# tm4cShield_v2_0.net
KiCad netlist of a schematic drawn in EAGLE
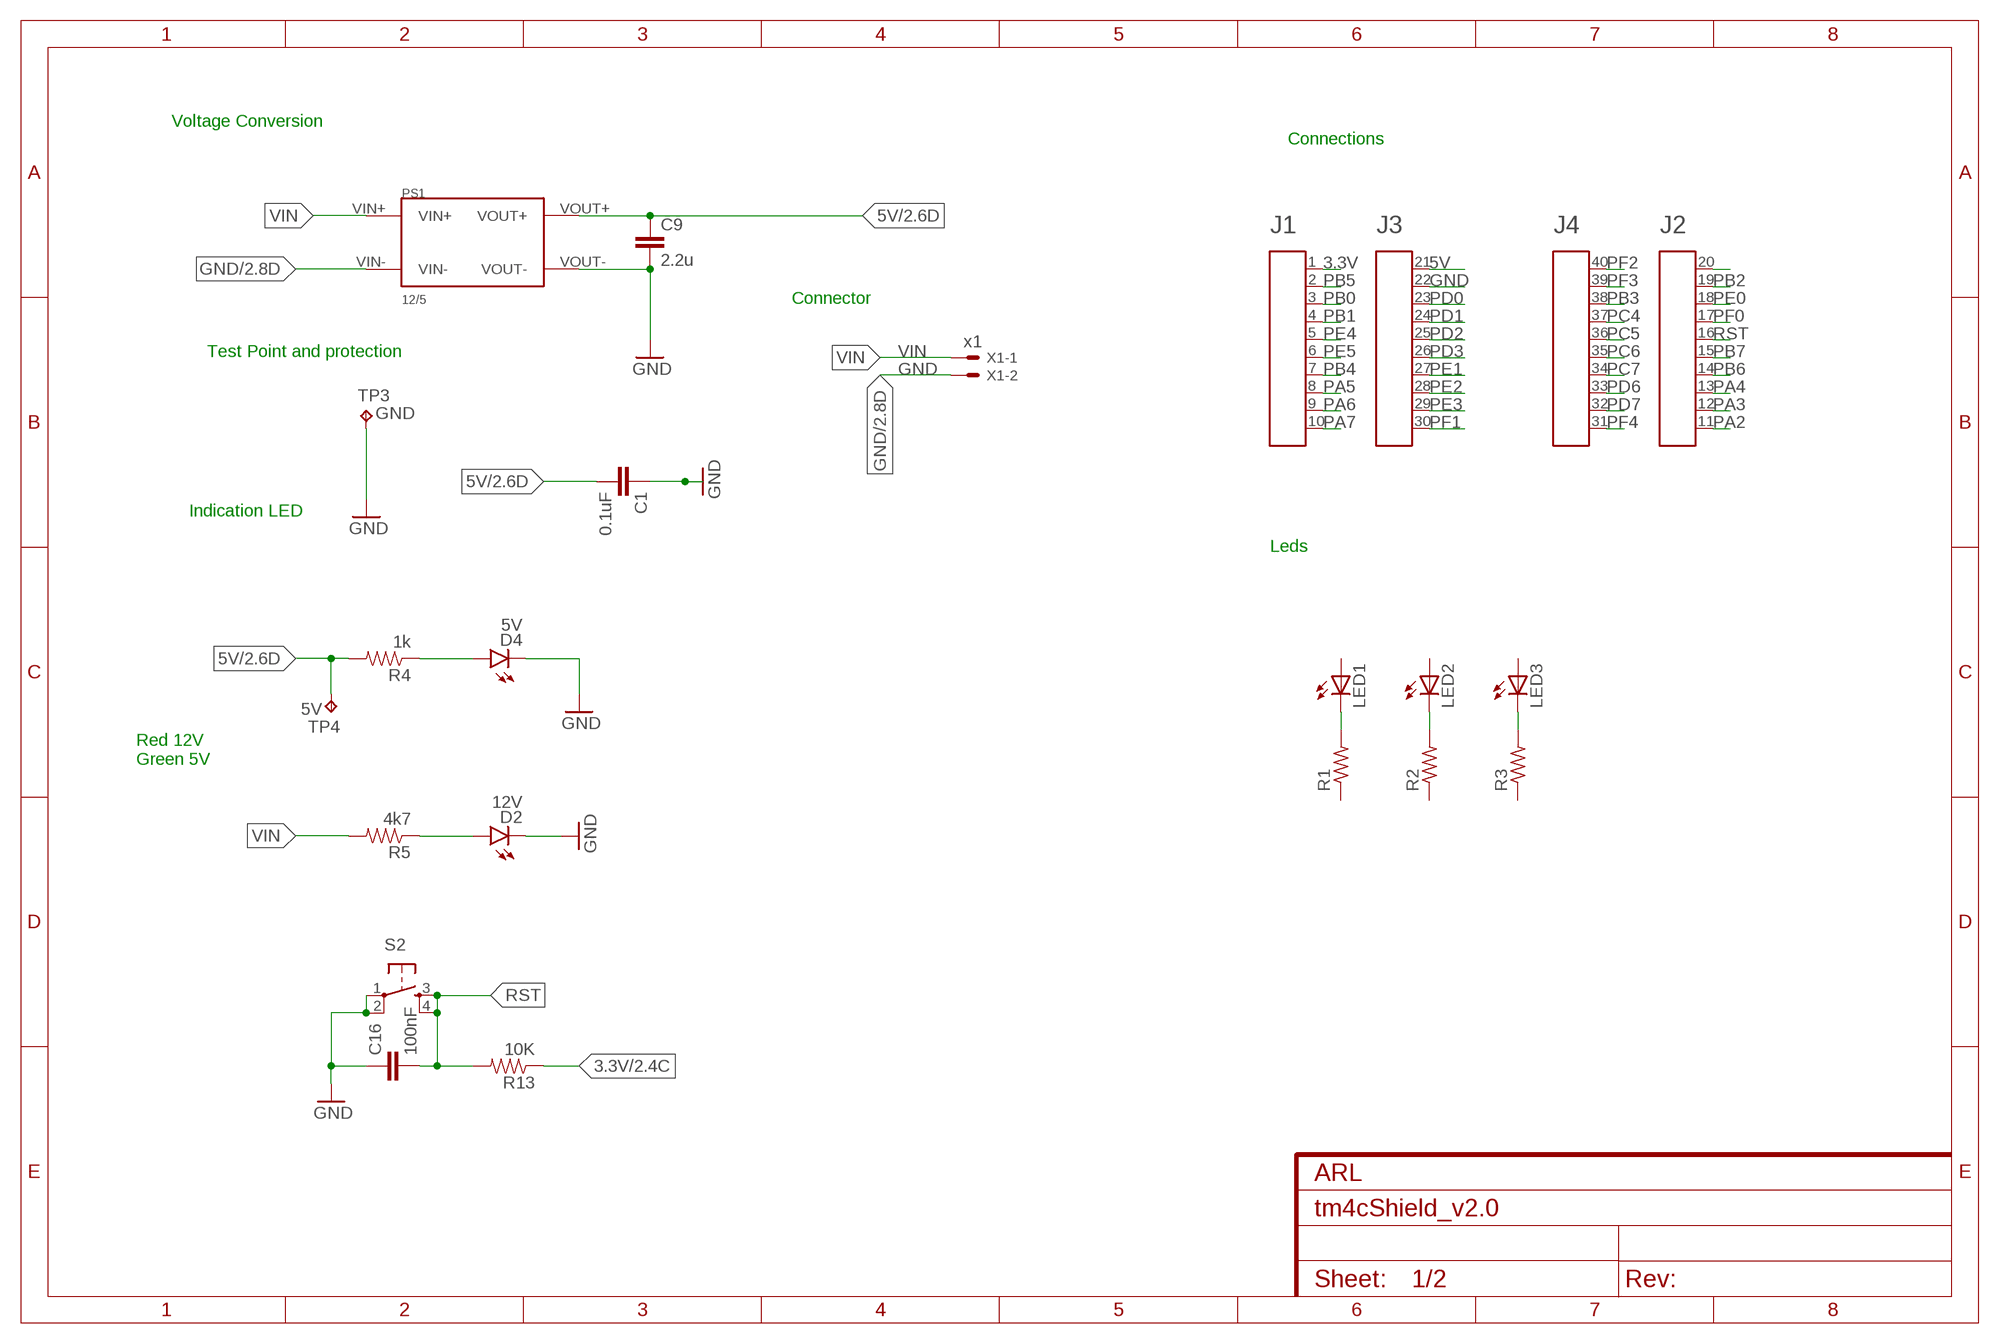
[diagram p0: schematic, sheet 1]
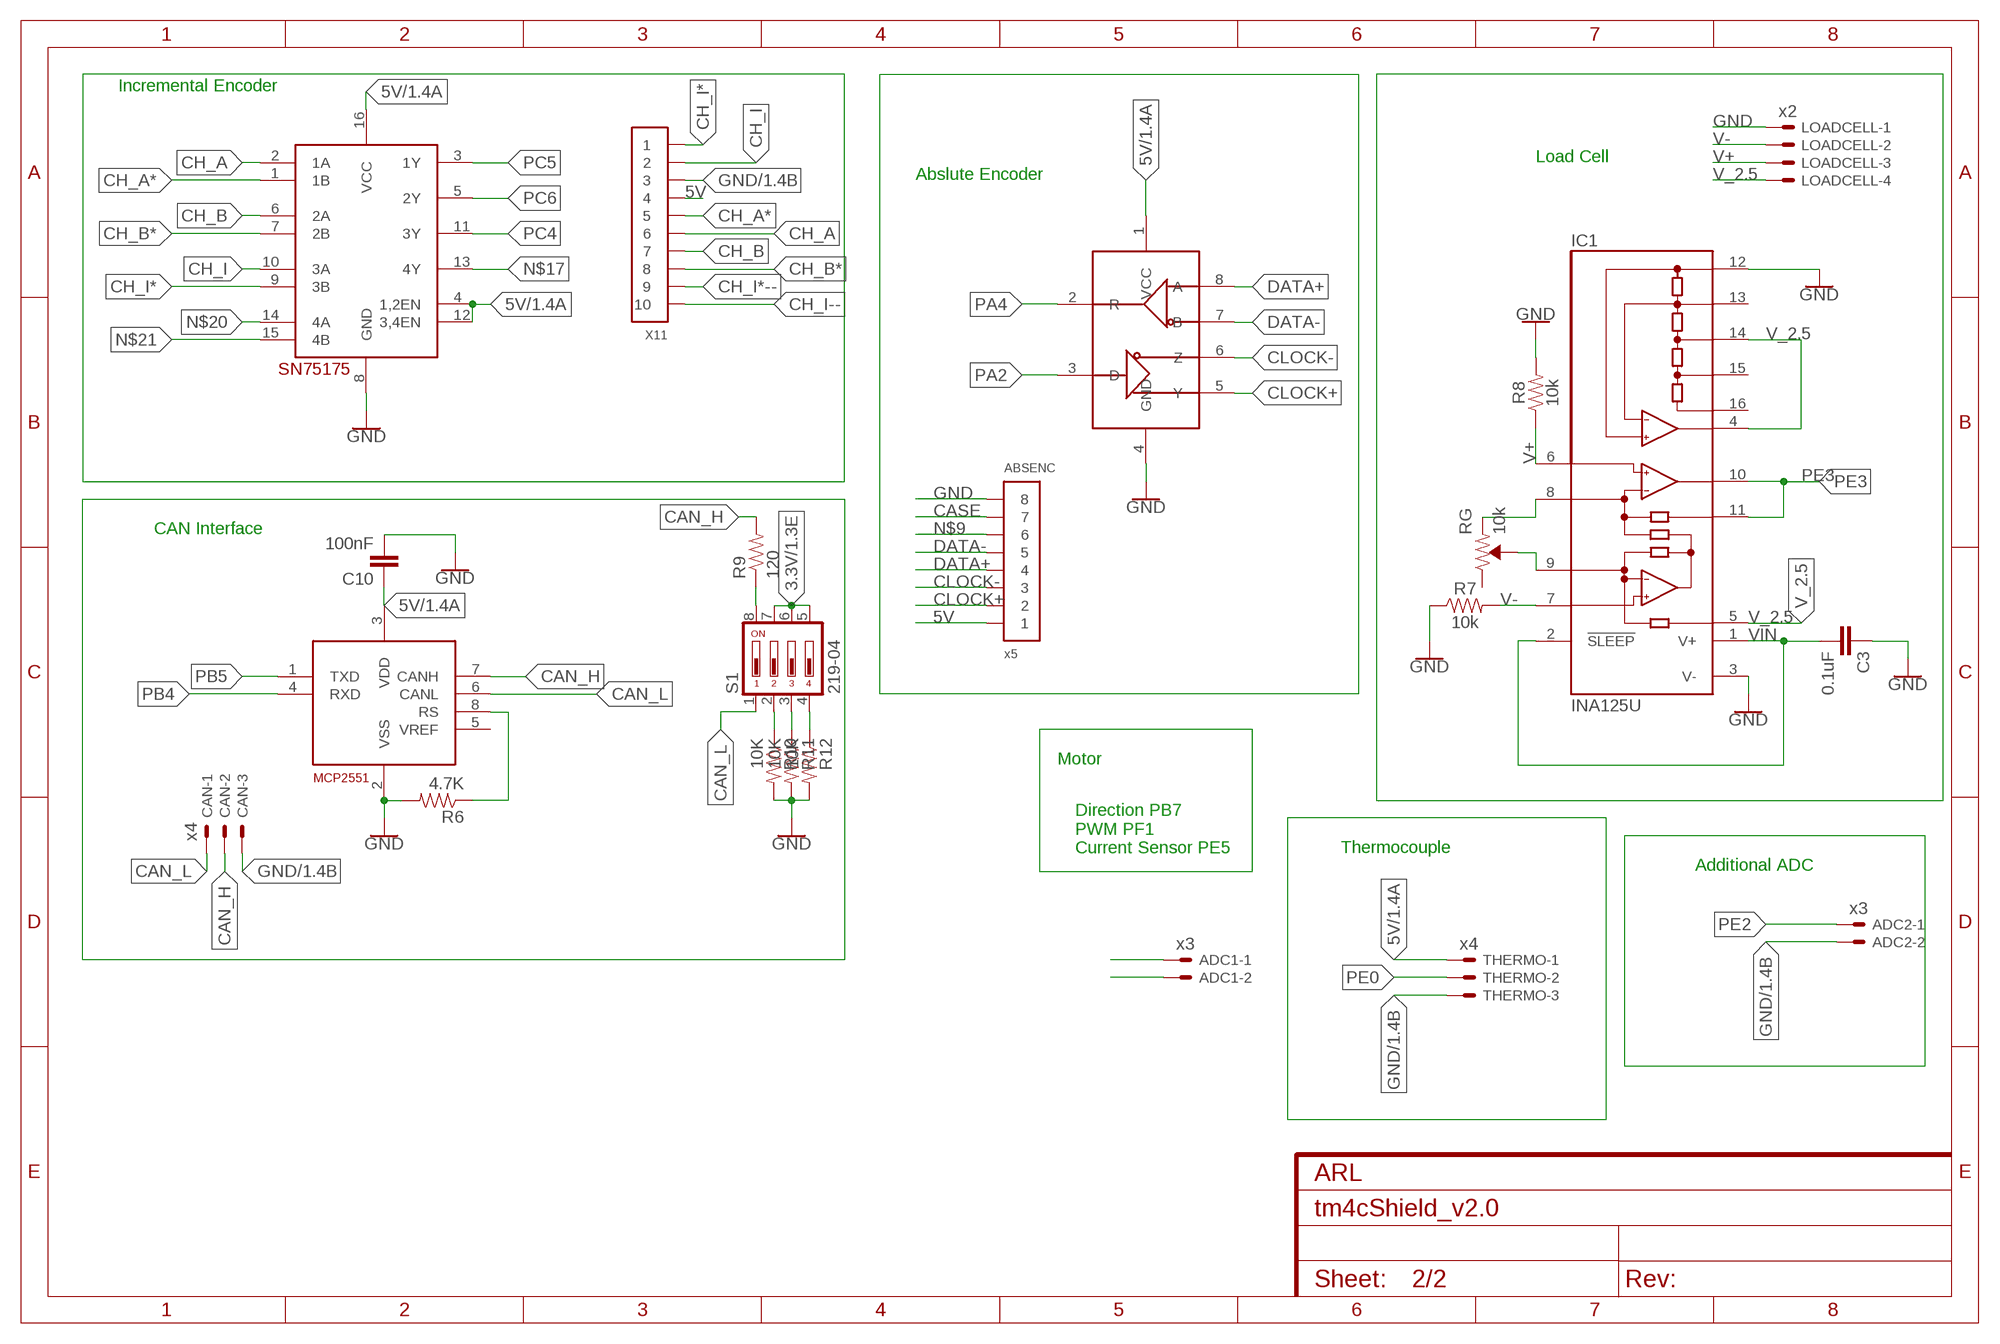
[diagram p1: schematic, sheet 2]

(export (version "E")
  (design (tool "Eeschema 10.0.6"))
  (components
    (comp (ref "ABSENC")
      (value "x5")
      (footprint "eagle-import:PB-53261-08")
      (fields (field (name "PARTNO") "0532610871"))
      (libsource (lib "eagle-import") (part "CONN_8-1-53261"))
    )
    (comp (ref "ADC1")
      (value "x3")
      (footprint "eagle-import:53261-02")
      (libsource (lib "eagle-import") (part "53?-02261"))
    )
    (comp (ref "ADC2")
      (value "x3")
      (footprint "eagle-import:53261-02")
      (libsource (lib "eagle-import") (part "53?-02261"))
    )
    (comp (ref "C3")
      (value "0.1uF")
      (footprint "eagle-import:0603")
      (libsource (lib "eagle-import") (part "0.1UF-0603-25V-(+80/-20%)"))
    )
    (comp (ref "C10")
      (value "100nF")
      (footprint "eagle-import:0603-CAP")
      (fields (field (name "PARTNO") "C1608X7R1E104K"))
      (libsource (lib "eagle-import") (part "CAP0603-CAP"))
    )
    (comp (ref "CAN")
      (value "x4")
      (footprint "eagle-import:53261-03")
      (fields (field (name "MF") "MOLEX") (field (name "MPN") "53261-0390"))
      (libsource (lib "eagle-import") (part "53?-03261"))
    )
    (comp (ref "IC1")
      (value "INA125U")
      (footprint "eagle-import:SO16-1")
      (fields (field (name "MF") "TEXAS INSTRUMENT CONNECTORS"))
      (libsource (lib "eagle-import") (part "INA125U"))
    )
    (comp (ref "LOADCELL")
      (value "x2")
      (footprint "eagle-import:53261-04")
      (libsource (lib "eagle-import") (part "53?-04261"))
    )
    (comp (ref "R6")
      (value "4.7K")
      (footprint "eagle-import:0603-RES")
      (fields (field (name "PARTNO") "ERJ-3EKF4701V"))
      (libsource (lib "eagle-import") (part "RESISTOR0603-RES"))
    )
    (comp (ref "R7")
      (value "10k")
      (footprint "eagle-import:0603")
      (libsource (lib "eagle-import") (part "0.05OHM-0603-1/5W-1%"))
    )
    (comp (ref "R8")
      (value "10k")
      (footprint "eagle-import:0603")
      (libsource (lib "eagle-import") (part "0.05OHM-0603-1/5W-1%"))
    )
    (comp (ref "R9")
      (value "120")
      (footprint "eagle-import:0603-RES")
      (fields (field (name "PARTNO") "ERJ-3GEYJ121V"))
      (libsource (lib "eagle-import") (part "RESISTOR0603-RES"))
    )
    (comp (ref "R10")
      (value "10K")
      (footprint "eagle-import:0603-RES")
      (fields (field (name "PARTNO") "ERJ-3EKF1002V"))
      (libsource (lib "eagle-import") (part "RESISTOR0603-RES"))
    )
    (comp (ref "R11")
      (value "10K")
      (footprint "eagle-import:0603-RES")
      (fields (field (name "PARTNO") "ERJ-3EKF1002V"))
      (libsource (lib "eagle-import") (part "RESISTOR0603-RES"))
    )
    (comp (ref "R12")
      (value "10K")
      (footprint "eagle-import:0603-RES")
      (fields (field (name "PARTNO") "ERJ-3EKF1002V"))
      (libsource (lib "eagle-import") (part "RESISTOR0603-RES"))
    )
    (comp (ref "RG")
      (value "10k")
      (footprint "eagle-import:TRIMPOT-PTH-3386U")
      (libsource (lib "eagle-import") (part "TRIMPOT-PTH-10MM-KNOB-1/2W-10%"))
    )
    (comp (ref "S1")
      (value "219-04")
      (footprint "eagle-import:CTS-219-04")
      (fields (field (name "PARTNO") "219-4LPST"))
      (libsource (lib "eagle-import") (part "219-04"))
    )
    (comp (ref "THERMO")
      (value "x4")
      (footprint "eagle-import:53261-03")
      (fields (field (name "MF") "MOLEX") (field (name "MPN") "53261-0390"))
      (libsource (lib "eagle-import") (part "53?-03261"))
    )
    (comp (ref "U$2")
      (value "SN75175")
      (footprint "eagle-import:SOIC16")
      (fields (field (name "PARTNO") "SN75175DR"))
      (libsource (lib "eagle-import") (part "SN75175"))
    )
    (comp (ref "U$4")
      (value "SP490")
      (footprint "eagle-import:SOIC8")
      (fields (field (name "PARTNO") "SP490CN-L"))
      (libsource (lib "eagle-import") (part "SP490"))
    )
    (comp (ref "U2")
      (value "MCP2551")
      (footprint "eagle-import:SOIC8")
      (fields (field (name "PARTNO") "MCP2551-I/SN"))
      (libsource (lib "eagle-import") (part "MCP2551"))
    )
    (comp (ref "X11")
      (value "CONN_10-1-53261")
      (footprint "eagle-import:PB-53261-10")
      (fields (field (name "PARTNO") "0532611071"))
      (libsource (lib "eagle-import") (part "CONN_10-1-53261"))
    )
    (comp (ref "A1")
      (value "HEADER4X10-BOOSTERPACK")
      (footprint "eagle-import:4X10-BOOSTERPACK")
      (libsource (lib "eagle-import") (part "HEADER4X10-BOOSTERPACK"))
    )
    (comp (ref "C1")
      (value "0.1uF")
      (footprint "eagle-import:0603")
      (libsource (lib "eagle-import") (part "0.1UF-0603-25V-(+80/-20%)"))
    )
    (comp (ref "C9")
      (value "2.2u")
      (footprint "eagle-import:0603-CAP")
      (fields (field (name "MPN") "GRM188R61H225KE11D"))
      (libsource (lib "eagle-import") (part "2.2U_CAPACITOR_0603"))
    )
    (comp (ref "C16")
      (value "100nF")
      (footprint "eagle-import:0603-CAP")
      (fields (field (name "PARTNO") "C1608X7R1E104K"))
      (libsource (lib "eagle-import") (part "SparkFun-Passives_CAP0603-CAP"))
    )
    (comp (ref "D2")
      (value "12V")
      (footprint "eagle-import:LED-0603")
      (fields (field (name "MPN") "LY L296-Q2R2-26-Z"))
      (libsource (lib "eagle-import") (part "YELLOW_LED_0603"))
    )
    (comp (ref "D4")
      (value "5V")
      (footprint "eagle-import:LED-0603")
      (fields (field (name "MPN") "LB L293-M2P1-36-1-Z"))
      (libsource (lib "eagle-import") (part "BLUE_LED_0603"))
    )
    (comp (ref "LED1")
      (value "LED0603")
      (footprint "eagle-import:LED-0603")
      (libsource (lib "eagle-import") (part "LED0603"))
    )
    (comp (ref "LED2")
      (value "LED0603")
      (footprint "eagle-import:LED-0603")
      (libsource (lib "eagle-import") (part "LED0603"))
    )
    (comp (ref "LED3")
      (value "LED0603")
      (footprint "eagle-import:LED-0603")
      (libsource (lib "eagle-import") (part "LED0603"))
    )
    (comp (ref "PS1")
      (value "12/5")
      (footprint "eagle-import:MURATA_NMG")
      (fields (field (name "MPN") "NMG2405SC "))
      (libsource (lib "eagle-import") (part "MURATA_NMG2405SC"))
    )
    (comp (ref "R1")
      (value "RESISTOR_0603")
      (footprint "eagle-import:RESC0603")
      (libsource (lib "eagle-import") (part "RESISTOR_0603"))
    )
    (comp (ref "R2")
      (value "RESISTOR_0603")
      (footprint "eagle-import:RESC0603")
      (libsource (lib "eagle-import") (part "RESISTOR_0603"))
    )
    (comp (ref "R3")
      (value "RESISTOR_0603")
      (footprint "eagle-import:RESC0603")
      (libsource (lib "eagle-import") (part "RESISTOR_0603"))
    )
    (comp (ref "R4")
      (value "1k")
      (footprint "eagle-import:0603-RES")
      (fields (field (name "MPN") "CRCW06031K00FKEA"))
      (libsource (lib "eagle-import") (part "1K_RESISTOR_0603"))
    )
    (comp (ref "R5")
      (value "4k7")
      (footprint "eagle-import:0603-RES")
      (fields (field (name "MPN") "CRCW06034K70FKEA"))
      (libsource (lib "eagle-import") (part "4K7_RESISTOR_0603"))
    )
    (comp (ref "R13")
      (value "10K")
      (footprint "eagle-import:0603-RES")
      (fields (field (name "PARTNO") "ERJ-3EKF1002V"))
      (libsource (lib "eagle-import") (part "SparkFun-Passives_RESISTOR0603-RES"))
    )
    (comp (ref "S2")
      (value "TAC_SWITCHPTH")
      (footprint "eagle-import:TACTILE-PTH")
      (fields (field (name "PARTNO") "B3F-1005"))
      (libsource (lib "eagle-import") (part "TAC_SWITCHPTH"))
    )
    (comp (ref "TP3")
      (value "GND")
      (footprint "eagle-import:5000_SERIES_TESTPOINT")
      (fields (field (name "MPN") "5002"))
      (libsource (lib "eagle-import") (part "TP5000"))
    )
    (comp (ref "TP4")
      (value "5V")
      (footprint "eagle-import:5000_SERIES_TESTPOINT")
      (fields (field (name "MPN") "5002"))
      (libsource (lib "eagle-import") (part "TP5000"))
    )
    (comp (ref "X1")
      (value "x1")
      (footprint "eagle-import:53261-02")
      (libsource (lib "eagle-import") (part "53?-02261"))
    )
  )
  (nets
    (net (code "1") (name "3.3V") (class "Default")
      (node (ref "A1") (pin "1") (pinfunction "P$1_1") (pintype "bidirectional"))
      (node (ref "R13") (pin "1") (pinfunction "1_1") (pintype "passive"))
      (node (ref "S1") (pin "5") (pinfunction "5_5") (pintype "passive"))
      (node (ref "S1") (pin "6") (pinfunction "6_6") (pintype "passive"))
      (node (ref "S1") (pin "7") (pinfunction "7_7") (pintype "passive"))
    )
    (net (code "2") (name "5V") (class "Default")
      (node (ref "A1") (pin "21") (pinfunction "P$21_21") (pintype "bidirectional"))
      (node (ref "ABSENC") (pin "1") (pinfunction "1_1") (pintype "bidirectional"))
      (node (ref "C1") (pin "2") (pinfunction "2_2") (pintype "passive"))
      (node (ref "C10") (pin "1") (pinfunction "1_1") (pintype "passive"))
      (node (ref "C9") (pin "1") (pinfunction "1_1") (pintype "passive"))
      (node (ref "PS1") (pin "VOUT+") (pinfunction "VOUT+_VOUT+") (pintype "bidirectional"))
      (node (ref "R4") (pin "2") (pinfunction "2_2") (pintype "passive"))
      (node (ref "THERMO") (pin "1") (pinfunction "S_1") (pintype "passive"))
      (node (ref "TP4") (pin "P$1") (pinfunction "TP_P$1") (pintype "input"))
      (node (ref "U$2") (pin "12") (pinfunction "3,4EN_12") (pintype "bidirectional"))
      (node (ref "U$2") (pin "16") (pinfunction "VCC_16") (pintype "bidirectional"))
      (node (ref "U$2") (pin "4") (pinfunction "1,2EN_4") (pintype "bidirectional"))
      (node (ref "U$4") (pin "1") (pinfunction "VCC_1") (pintype "bidirectional"))
      (node (ref "U2") (pin "3") (pinfunction "VDD_3") (pintype "bidirectional"))
      (node (ref "X11") (pin "4") (pinfunction "4_4") (pintype "bidirectional"))
    )
    (net (code "3") (name "CAN_H") (class "Default")
      (node (ref "CAN") (pin "2") (pinfunction "S_2") (pintype "passive"))
      (node (ref "R9") (pin "2") (pinfunction "2_2") (pintype "passive"))
      (node (ref "U2") (pin "7") (pinfunction "CANH_7") (pintype "bidirectional"))
    )
    (net (code "4") (name "CAN_L") (class "Default")
      (node (ref "CAN") (pin "1") (pinfunction "S_1") (pintype "passive"))
      (node (ref "S1") (pin "1") (pinfunction "1_1") (pintype "passive"))
      (node (ref "U2") (pin "6") (pinfunction "CANL_6") (pintype "bidirectional"))
    )
    (net (code "5") (name "CASE") (class "Default")
      (node (ref "ABSENC") (pin "7") (pinfunction "7_7") (pintype "bidirectional"))
    )
    (net (code "6") (name "CH_A") (class "Default")
      (node (ref "U$2") (pin "2") (pinfunction "1A_2") (pintype "bidirectional"))
      (node (ref "X11") (pin "6") (pinfunction "6_6") (pintype "bidirectional"))
    )
    (net (code "7") (name "CH_A*") (class "Default")
      (node (ref "U$2") (pin "1") (pinfunction "1B_1") (pintype "bidirectional"))
      (node (ref "X11") (pin "5") (pinfunction "5_5") (pintype "bidirectional"))
    )
    (net (code "8") (name "CH_B") (class "Default")
      (node (ref "U$2") (pin "6") (pinfunction "2A_6") (pintype "bidirectional"))
      (node (ref "X11") (pin "7") (pinfunction "7_7") (pintype "bidirectional"))
    )
    (net (code "9") (name "CH_B*") (class "Default")
      (node (ref "U$2") (pin "7") (pinfunction "2B_7") (pintype "bidirectional"))
      (node (ref "X11") (pin "8") (pinfunction "8_8") (pintype "bidirectional"))
    )
    (net (code "10") (name "CH_I") (class "Default")
      (node (ref "U$2") (pin "10") (pinfunction "3A_10") (pintype "bidirectional"))
      (node (ref "X11") (pin "2") (pinfunction "2_2") (pintype "bidirectional"))
    )
    (net (code "11") (name "CH_I*") (class "Default")
      (node (ref "U$2") (pin "9") (pinfunction "3B_9") (pintype "bidirectional"))
      (node (ref "X11") (pin "1") (pinfunction "1_1") (pintype "bidirectional"))
    )
    (net (code "12") (name "CH_I*--") (class "Default")
      (node (ref "X11") (pin "9") (pinfunction "9_9") (pintype "bidirectional"))
    )
    (net (code "13") (name "CH_I--") (class "Default")
      (node (ref "X11") (pin "10") (pinfunction "10_10") (pintype "bidirectional"))
    )
    (net (code "14") (name "CLOCK+") (class "Default")
      (node (ref "ABSENC") (pin "2") (pinfunction "2_2") (pintype "bidirectional"))
      (node (ref "U$4") (pin "5") (pinfunction "Y_5") (pintype "bidirectional"))
    )
    (net (code "15") (name "CLOCK-") (class "Default")
      (node (ref "ABSENC") (pin "3") (pinfunction "3_3") (pintype "bidirectional"))
      (node (ref "U$4") (pin "6") (pinfunction "Z_6") (pintype "bidirectional"))
    )
    (net (code "16") (name "DATA+") (class "Default")
      (node (ref "ABSENC") (pin "4") (pinfunction "4_4") (pintype "bidirectional"))
      (node (ref "U$4") (pin "8") (pinfunction "A_8") (pintype "bidirectional"))
    )
    (net (code "17") (name "DATA-") (class "Default")
      (node (ref "ABSENC") (pin "5") (pinfunction "5_5") (pintype "bidirectional"))
      (node (ref "U$4") (pin "7") (pinfunction "B_7") (pintype "bidirectional"))
    )
    (net (code "18") (name "GND") (class "Default")
      (node (ref "A1") (pin "22") (pinfunction "P$22_22") (pintype "bidirectional"))
      (node (ref "ABSENC") (pin "8") (pinfunction "8_8") (pintype "bidirectional"))
      (node (ref "ADC2") (pin "2") (pinfunction "S_2") (pintype "passive"))
      (node (ref "C1") (pin "1") (pinfunction "1_1") (pintype "passive"))
      (node (ref "C10") (pin "2") (pinfunction "2_2") (pintype "passive"))
      (node (ref "C16") (pin "1") (pinfunction "1_1") (pintype "passive"))
      (node (ref "C3") (pin "1") (pinfunction "1_1") (pintype "passive"))
      (node (ref "C9") (pin "2") (pinfunction "2_2") (pintype "passive"))
      (node (ref "CAN") (pin "3") (pinfunction "S_3") (pintype "passive"))
      (node (ref "D2") (pin "C") (pinfunction "C_C") (pintype "passive"))
      (node (ref "D4") (pin "C") (pinfunction "C_C") (pintype "passive"))
      (node (ref "IC1") (pin "12") (pinfunction "REFCOM_12") (pintype "passive"))
      (node (ref "IC1") (pin "3") (pinfunction "V-_3") (pintype "power_in"))
      (node (ref "LOADCELL") (pin "1") (pinfunction "S_1") (pintype "passive"))
      (node (ref "PS1") (pin "VIN-") (pinfunction "VIN-_VIN-") (pintype "bidirectional"))
      (node (ref "PS1") (pin "VOUT-") (pinfunction "VOUT-_VOUT-") (pintype "bidirectional"))
      (node (ref "R10") (pin "2") (pinfunction "2_2") (pintype "passive"))
      (node (ref "R11") (pin "2") (pinfunction "2_2") (pintype "passive"))
      (node (ref "R12") (pin "2") (pinfunction "2_2") (pintype "passive"))
      (node (ref "R6") (pin "2") (pinfunction "2_2") (pintype "passive"))
      (node (ref "R7") (pin "1") (pinfunction "1_1") (pintype "passive"))
      (node (ref "R8") (pin "2") (pinfunction "2_2") (pintype "passive"))
      (node (ref "S2") (pin "1") (pinfunction "1_1") (pintype "passive"))
      (node (ref "S2") (pin "2") (pinfunction "2_2") (pintype "passive"))
      (node (ref "THERMO") (pin "3") (pinfunction "S_3") (pintype "passive"))
      (node (ref "TP3") (pin "P$1") (pinfunction "TP_P$1") (pintype "input"))
      (node (ref "U$2") (pin "8") (pinfunction "GND_8") (pintype "bidirectional"))
      (node (ref "U$4") (pin "4") (pinfunction "GND_4") (pintype "bidirectional"))
      (node (ref "U2") (pin "2") (pinfunction "VSS_2") (pintype "bidirectional"))
      (node (ref "X1") (pin "2") (pinfunction "S_2") (pintype "passive"))
      (node (ref "X11") (pin "3") (pinfunction "3_3") (pintype "bidirectional"))
    )
    (net (code "19") (name "N$9") (class "Default")
      (node (ref "ABSENC") (pin "6") (pinfunction "6_6") (pintype "bidirectional"))
    )
    (net (code "20") (name "N$17") (class "Default")
      (node (ref "U$2") (pin "13") (pinfunction "4Y_13") (pintype "bidirectional"))
    )
    (net (code "21") (name "N$20") (class "Default")
      (node (ref "U$2") (pin "14") (pinfunction "4A_14") (pintype "bidirectional"))
    )
    (net (code "22") (name "N$21") (class "Default")
      (node (ref "U$2") (pin "15") (pinfunction "4B_15") (pintype "bidirectional"))
    )
    (net (code "23") (name "Net-(D2-PadA)") (class "Default")
      (node (ref "D2") (pin "A") (pinfunction "A_A") (pintype "passive"))
      (node (ref "R5") (pin "1") (pinfunction "1_1") (pintype "passive"))
    )
    (net (code "24") (name "Net-(D4-PadA)") (class "Default")
      (node (ref "D4") (pin "A") (pinfunction "A_A") (pintype "passive"))
      (node (ref "R4") (pin "1") (pinfunction "1_1") (pintype "passive"))
    )
    (net (code "25") (name "Net-(LED1-PadC)") (class "Default")
      (node (ref "LED1") (pin "C") (pinfunction "C_C") (pintype "passive"))
      (node (ref "R1") (pin "2") (pinfunction "2_2") (pintype "passive"))
    )
    (net (code "26") (name "Net-(LED2-PadC)") (class "Default")
      (node (ref "LED2") (pin "C") (pinfunction "C_C") (pintype "passive"))
      (node (ref "R2") (pin "2") (pinfunction "2_2") (pintype "passive"))
    )
    (net (code "27") (name "Net-(LED3-PadC)") (class "Default")
      (node (ref "LED3") (pin "C") (pinfunction "C_C") (pintype "passive"))
      (node (ref "R3") (pin "2") (pinfunction "2_2") (pintype "passive"))
    )
    (net (code "28") (name "Net-(R9-Pad1)") (class "Default")
      (node (ref "R9") (pin "1") (pinfunction "1_1") (pintype "passive"))
      (node (ref "S1") (pin "8") (pinfunction "8_8") (pintype "passive"))
    )
    (net (code "29") (name "Net-(R10-Pad1)") (class "Default")
      (node (ref "R10") (pin "1") (pinfunction "1_1") (pintype "passive"))
      (node (ref "S1") (pin "2") (pinfunction "2_2") (pintype "passive"))
    )
    (net (code "30") (name "Net-(R11-Pad1)") (class "Default")
      (node (ref "R11") (pin "1") (pinfunction "1_1") (pintype "passive"))
      (node (ref "S1") (pin "3") (pinfunction "3_3") (pintype "passive"))
    )
    (net (code "31") (name "Net-(R12-Pad1)") (class "Default")
      (node (ref "R12") (pin "1") (pinfunction "1_1") (pintype "passive"))
      (node (ref "S1") (pin "4") (pinfunction "4_4") (pintype "passive"))
    )
    (net (code "32") (name "Net-(RG-CCW)") (class "Default")
      (node (ref "IC1") (pin "8") (pinfunction "RG_8") (pintype "passive"))
      (node (ref "RG") (pin "1") (pinfunction "CCW_1") (pintype "passive"))
    )
    (net (code "33") (name "Net-(RG-WIPER)") (class "Default")
      (node (ref "IC1") (pin "9") (pinfunction "RG_9") (pintype "passive"))
      (node (ref "RG") (pin "2") (pinfunction "WIPER_2") (pintype "passive"))
    )
    (net (code "34") (name "Net-(U2-RS)") (class "Default")
      (node (ref "R6") (pin "1") (pinfunction "1_1") (pintype "passive"))
      (node (ref "U2") (pin "8") (pinfunction "RS_8") (pintype "bidirectional"))
    )
    (net (code "35") (name "PA2") (class "Default")
      (node (ref "A1") (pin "11") (pinfunction "P$11_11") (pintype "bidirectional"))
      (node (ref "U$4") (pin "3") (pinfunction "D_3") (pintype "bidirectional"))
    )
    (net (code "36") (name "PA3") (class "Default")
      (node (ref "A1") (pin "12") (pinfunction "P$12_12") (pintype "bidirectional"))
    )
    (net (code "37") (name "PA4") (class "Default")
      (node (ref "A1") (pin "13") (pinfunction "P$13_13") (pintype "bidirectional"))
      (node (ref "U$4") (pin "2") (pinfunction "R_2") (pintype "bidirectional"))
    )
    (net (code "38") (name "PA5") (class "Default")
      (node (ref "A1") (pin "8") (pinfunction "P$8_8") (pintype "bidirectional"))
    )
    (net (code "39") (name "PA6") (class "Default")
      (node (ref "A1") (pin "9") (pinfunction "P$9_9") (pintype "bidirectional"))
    )
    (net (code "40") (name "PA7") (class "Default")
      (node (ref "A1") (pin "10") (pinfunction "P$10_10") (pintype "bidirectional"))
    )
    (net (code "41") (name "PB0") (class "Default")
      (node (ref "A1") (pin "3") (pinfunction "P$3_3") (pintype "bidirectional"))
    )
    (net (code "42") (name "PB1") (class "Default")
      (node (ref "A1") (pin "4") (pinfunction "P$4_4") (pintype "bidirectional"))
    )
    (net (code "43") (name "PB2") (class "Default")
      (node (ref "A1") (pin "19") (pinfunction "P$19_19") (pintype "bidirectional"))
    )
    (net (code "44") (name "PB3") (class "Default")
      (node (ref "A1") (pin "38") (pinfunction "P$38_38") (pintype "bidirectional"))
    )
    (net (code "45") (name "PB4") (class "Default")
      (node (ref "A1") (pin "7") (pinfunction "P$7_7") (pintype "bidirectional"))
      (node (ref "U2") (pin "4") (pinfunction "RXD_4") (pintype "bidirectional"))
    )
    (net (code "46") (name "PB5") (class "Default")
      (node (ref "A1") (pin "2") (pinfunction "P$2_2") (pintype "bidirectional"))
      (node (ref "U2") (pin "1") (pinfunction "TXD_1") (pintype "bidirectional"))
    )
    (net (code "47") (name "PB6") (class "Default")
      (node (ref "A1") (pin "14") (pinfunction "P$14_14") (pintype "bidirectional"))
    )
    (net (code "48") (name "PB7") (class "Default")
      (node (ref "A1") (pin "15") (pinfunction "P$15_15") (pintype "bidirectional"))
    )
    (net (code "49") (name "PC4") (class "Default")
      (node (ref "A1") (pin "37") (pinfunction "P$37_37") (pintype "bidirectional"))
      (node (ref "U$2") (pin "11") (pinfunction "3Y_11") (pintype "bidirectional"))
    )
    (net (code "50") (name "PC5") (class "Default")
      (node (ref "A1") (pin "36") (pinfunction "P$36_36") (pintype "bidirectional"))
      (node (ref "U$2") (pin "3") (pinfunction "1Y_3") (pintype "bidirectional"))
    )
    (net (code "51") (name "PC6") (class "Default")
      (node (ref "A1") (pin "35") (pinfunction "P$35_35") (pintype "bidirectional"))
      (node (ref "U$2") (pin "5") (pinfunction "2Y_5") (pintype "bidirectional"))
    )
    (net (code "52") (name "PC7") (class "Default")
      (node (ref "A1") (pin "34") (pinfunction "P$34_34") (pintype "bidirectional"))
    )
    (net (code "53") (name "PD0") (class "Default")
      (node (ref "A1") (pin "23") (pinfunction "P$23_23") (pintype "bidirectional"))
    )
    (net (code "54") (name "PD1") (class "Default")
      (node (ref "A1") (pin "24") (pinfunction "P$24_24") (pintype "bidirectional"))
    )
    (net (code "55") (name "PD2") (class "Default")
      (node (ref "A1") (pin "25") (pinfunction "P$25_25") (pintype "bidirectional"))
    )
    (net (code "56") (name "PD3") (class "Default")
      (node (ref "A1") (pin "26") (pinfunction "P$26_26") (pintype "bidirectional"))
    )
    (net (code "57") (name "PD6") (class "Default")
      (node (ref "A1") (pin "33") (pinfunction "P$33_33") (pintype "bidirectional"))
    )
    (net (code "58") (name "PD7") (class "Default")
      (node (ref "A1") (pin "32") (pinfunction "P$32_32") (pintype "bidirectional"))
    )
    (net (code "59") (name "PE0") (class "Default")
      (node (ref "A1") (pin "18") (pinfunction "P$18_18") (pintype "bidirectional"))
      (node (ref "THERMO") (pin "2") (pinfunction "S_2") (pintype "passive"))
    )
    (net (code "60") (name "PE1") (class "Default")
      (node (ref "A1") (pin "27") (pinfunction "P$27_27") (pintype "bidirectional"))
    )
    (net (code "61") (name "PE2") (class "Default")
      (node (ref "A1") (pin "28") (pinfunction "P$28_28") (pintype "bidirectional"))
      (node (ref "ADC2") (pin "1") (pinfunction "S_1") (pintype "passive"))
    )
    (net (code "62") (name "PE3") (class "Default")
      (node (ref "A1") (pin "29") (pinfunction "P$29_29") (pintype "bidirectional"))
      (node (ref "IC1") (pin "10") (pinfunction "OUT_10") (pintype "output"))
      (node (ref "IC1") (pin "11") (pinfunction "SENSE_11") (pintype "passive"))
    )
    (net (code "63") (name "PE4") (class "Default")
      (node (ref "A1") (pin "5") (pinfunction "P$5_5") (pintype "bidirectional"))
    )
    (net (code "64") (name "PE5") (class "Default")
      (node (ref "A1") (pin "6") (pinfunction "P$6_6") (pintype "bidirectional"))
    )
    (net (code "65") (name "PF0") (class "Default")
      (node (ref "A1") (pin "17") (pinfunction "P$17_17") (pintype "bidirectional"))
    )
    (net (code "66") (name "PF1") (class "Default")
      (node (ref "A1") (pin "30") (pinfunction "P$30_30") (pintype "bidirectional"))
    )
    (net (code "67") (name "PF2") (class "Default")
      (node (ref "A1") (pin "40") (pinfunction "P$40_40") (pintype "bidirectional"))
    )
    (net (code "68") (name "PF3") (class "Default")
      (node (ref "A1") (pin "39") (pinfunction "P$39_39") (pintype "bidirectional"))
    )
    (net (code "69") (name "PF4") (class "Default")
      (node (ref "A1") (pin "31") (pinfunction "P$31_31") (pintype "bidirectional"))
    )
    (net (code "70") (name "RST") (class "Default")
      (node (ref "A1") (pin "16") (pinfunction "P$16_16") (pintype "bidirectional"))
      (node (ref "C16") (pin "2") (pinfunction "2_2") (pintype "passive"))
      (node (ref "R13") (pin "2") (pinfunction "2_2") (pintype "passive"))
      (node (ref "S2") (pin "3") (pinfunction "3_3") (pintype "passive"))
      (node (ref "S2") (pin "4") (pinfunction "4_4") (pintype "passive"))
    )
    (net (code "71") (name "V+") (class "Default")
      (node (ref "IC1") (pin "6") (pinfunction "+IN_6") (pintype "input"))
      (node (ref "LOADCELL") (pin "3") (pinfunction "S_3") (pintype "passive"))
      (node (ref "R8") (pin "1") (pinfunction "1_1") (pintype "passive"))
    )
    (net (code "72") (name "V-") (class "Default")
      (node (ref "IC1") (pin "7") (pinfunction "-IN_7") (pintype "input"))
      (node (ref "LOADCELL") (pin "2") (pinfunction "S_2") (pintype "passive"))
      (node (ref "R7") (pin "2") (pinfunction "2_2") (pintype "passive"))
    )
    (net (code "73") (name "VIN") (class "Default")
      (node (ref "C3") (pin "2") (pinfunction "2_2") (pintype "passive"))
      (node (ref "IC1") (pin "1") (pinfunction "V+_1") (pintype "power_in"))
      (node (ref "IC1") (pin "2") (pinfunction "~{SLEEP}_2") (pintype "input"))
      (node (ref "PS1") (pin "VIN+") (pinfunction "VIN+_VIN+") (pintype "bidirectional"))
      (node (ref "R5") (pin "2") (pinfunction "2_2") (pintype "passive"))
      (node (ref "X1") (pin "1") (pinfunction "S_1") (pintype "passive"))
    )
    (net (code "74") (name "V_2.5") (class "Default")
      (node (ref "IC1") (pin "14") (pinfunction "REF2.5_14") (pintype "output"))
      (node (ref "IC1") (pin "4") (pinfunction "REFOUT_4") (pintype "output"))
      (node (ref "IC1") (pin "5") (pinfunction "REF_5") (pintype "passive"))
      (node (ref "LOADCELL") (pin "4") (pinfunction "S_4") (pintype "passive"))
    )
    (net (code "75") (name "unconnected-(A1-P$20-Pad20)") (class "Default")
      (node (ref "A1") (pin "20") (pinfunction "P$20_20") (pintype "bidirectional"))
    )
    (net (code "76") (name "unconnected-(ADC1A-S-Pad1)") (class "Default")
      (node (ref "ADC1") (pin "1") (pinfunction "S_1") (pintype "passive"))
    )
    (net (code "77") (name "unconnected-(ADC1B-S-Pad2)") (class "Default")
      (node (ref "ADC1") (pin "2") (pinfunction "S_2") (pintype "passive"))
    )
    (net (code "78") (name "unconnected-(IC1-REF5-Pad15)") (class "Default")
      (node (ref "IC1") (pin "15") (pinfunction "REF5_15") (pintype "output"))
    )
    (net (code "79") (name "unconnected-(IC1-REF10-Pad16)") (class "Default")
      (node (ref "IC1") (pin "16") (pinfunction "REF10_16") (pintype "output"))
    )
    (net (code "80") (name "unconnected-(IC1-REFBG-Pad13)") (class "Default")
      (node (ref "IC1") (pin "13") (pinfunction "REFBG_13") (pintype "output"))
    )
    (net (code "81") (name "unconnected-(LED1-PadA)") (class "Default")
      (node (ref "LED1") (pin "A") (pinfunction "A_A") (pintype "passive"))
    )
    (net (code "82") (name "unconnected-(LED2-PadA)") (class "Default")
      (node (ref "LED2") (pin "A") (pinfunction "A_A") (pintype "passive"))
    )
    (net (code "83") (name "unconnected-(LED3-PadA)") (class "Default")
      (node (ref "LED3") (pin "A") (pinfunction "A_A") (pintype "passive"))
    )
    (net (code "84") (name "unconnected-(R1-Pad1)") (class "Default")
      (node (ref "R1") (pin "1") (pinfunction "1_1") (pintype "passive"))
    )
    (net (code "85") (name "unconnected-(R2-Pad1)") (class "Default")
      (node (ref "R2") (pin "1") (pinfunction "1_1") (pintype "passive"))
    )
    (net (code "86") (name "unconnected-(R3-Pad1)") (class "Default")
      (node (ref "R3") (pin "1") (pinfunction "1_1") (pintype "passive"))
    )
    (net (code "87") (name "unconnected-(RG-CW-Pad3)") (class "Default")
      (node (ref "RG") (pin "3") (pinfunction "CW_3") (pintype "passive"))
    )
    (net (code "88") (name "unconnected-(U2-VREF-Pad5)") (class "Default")
      (node (ref "U2") (pin "5") (pinfunction "VREF_5") (pintype "bidirectional"))
    )
  )
)
